# SCH_SPD_PIR_HALL.net
KiCad netlist of a schematic drawn in EasyEDA
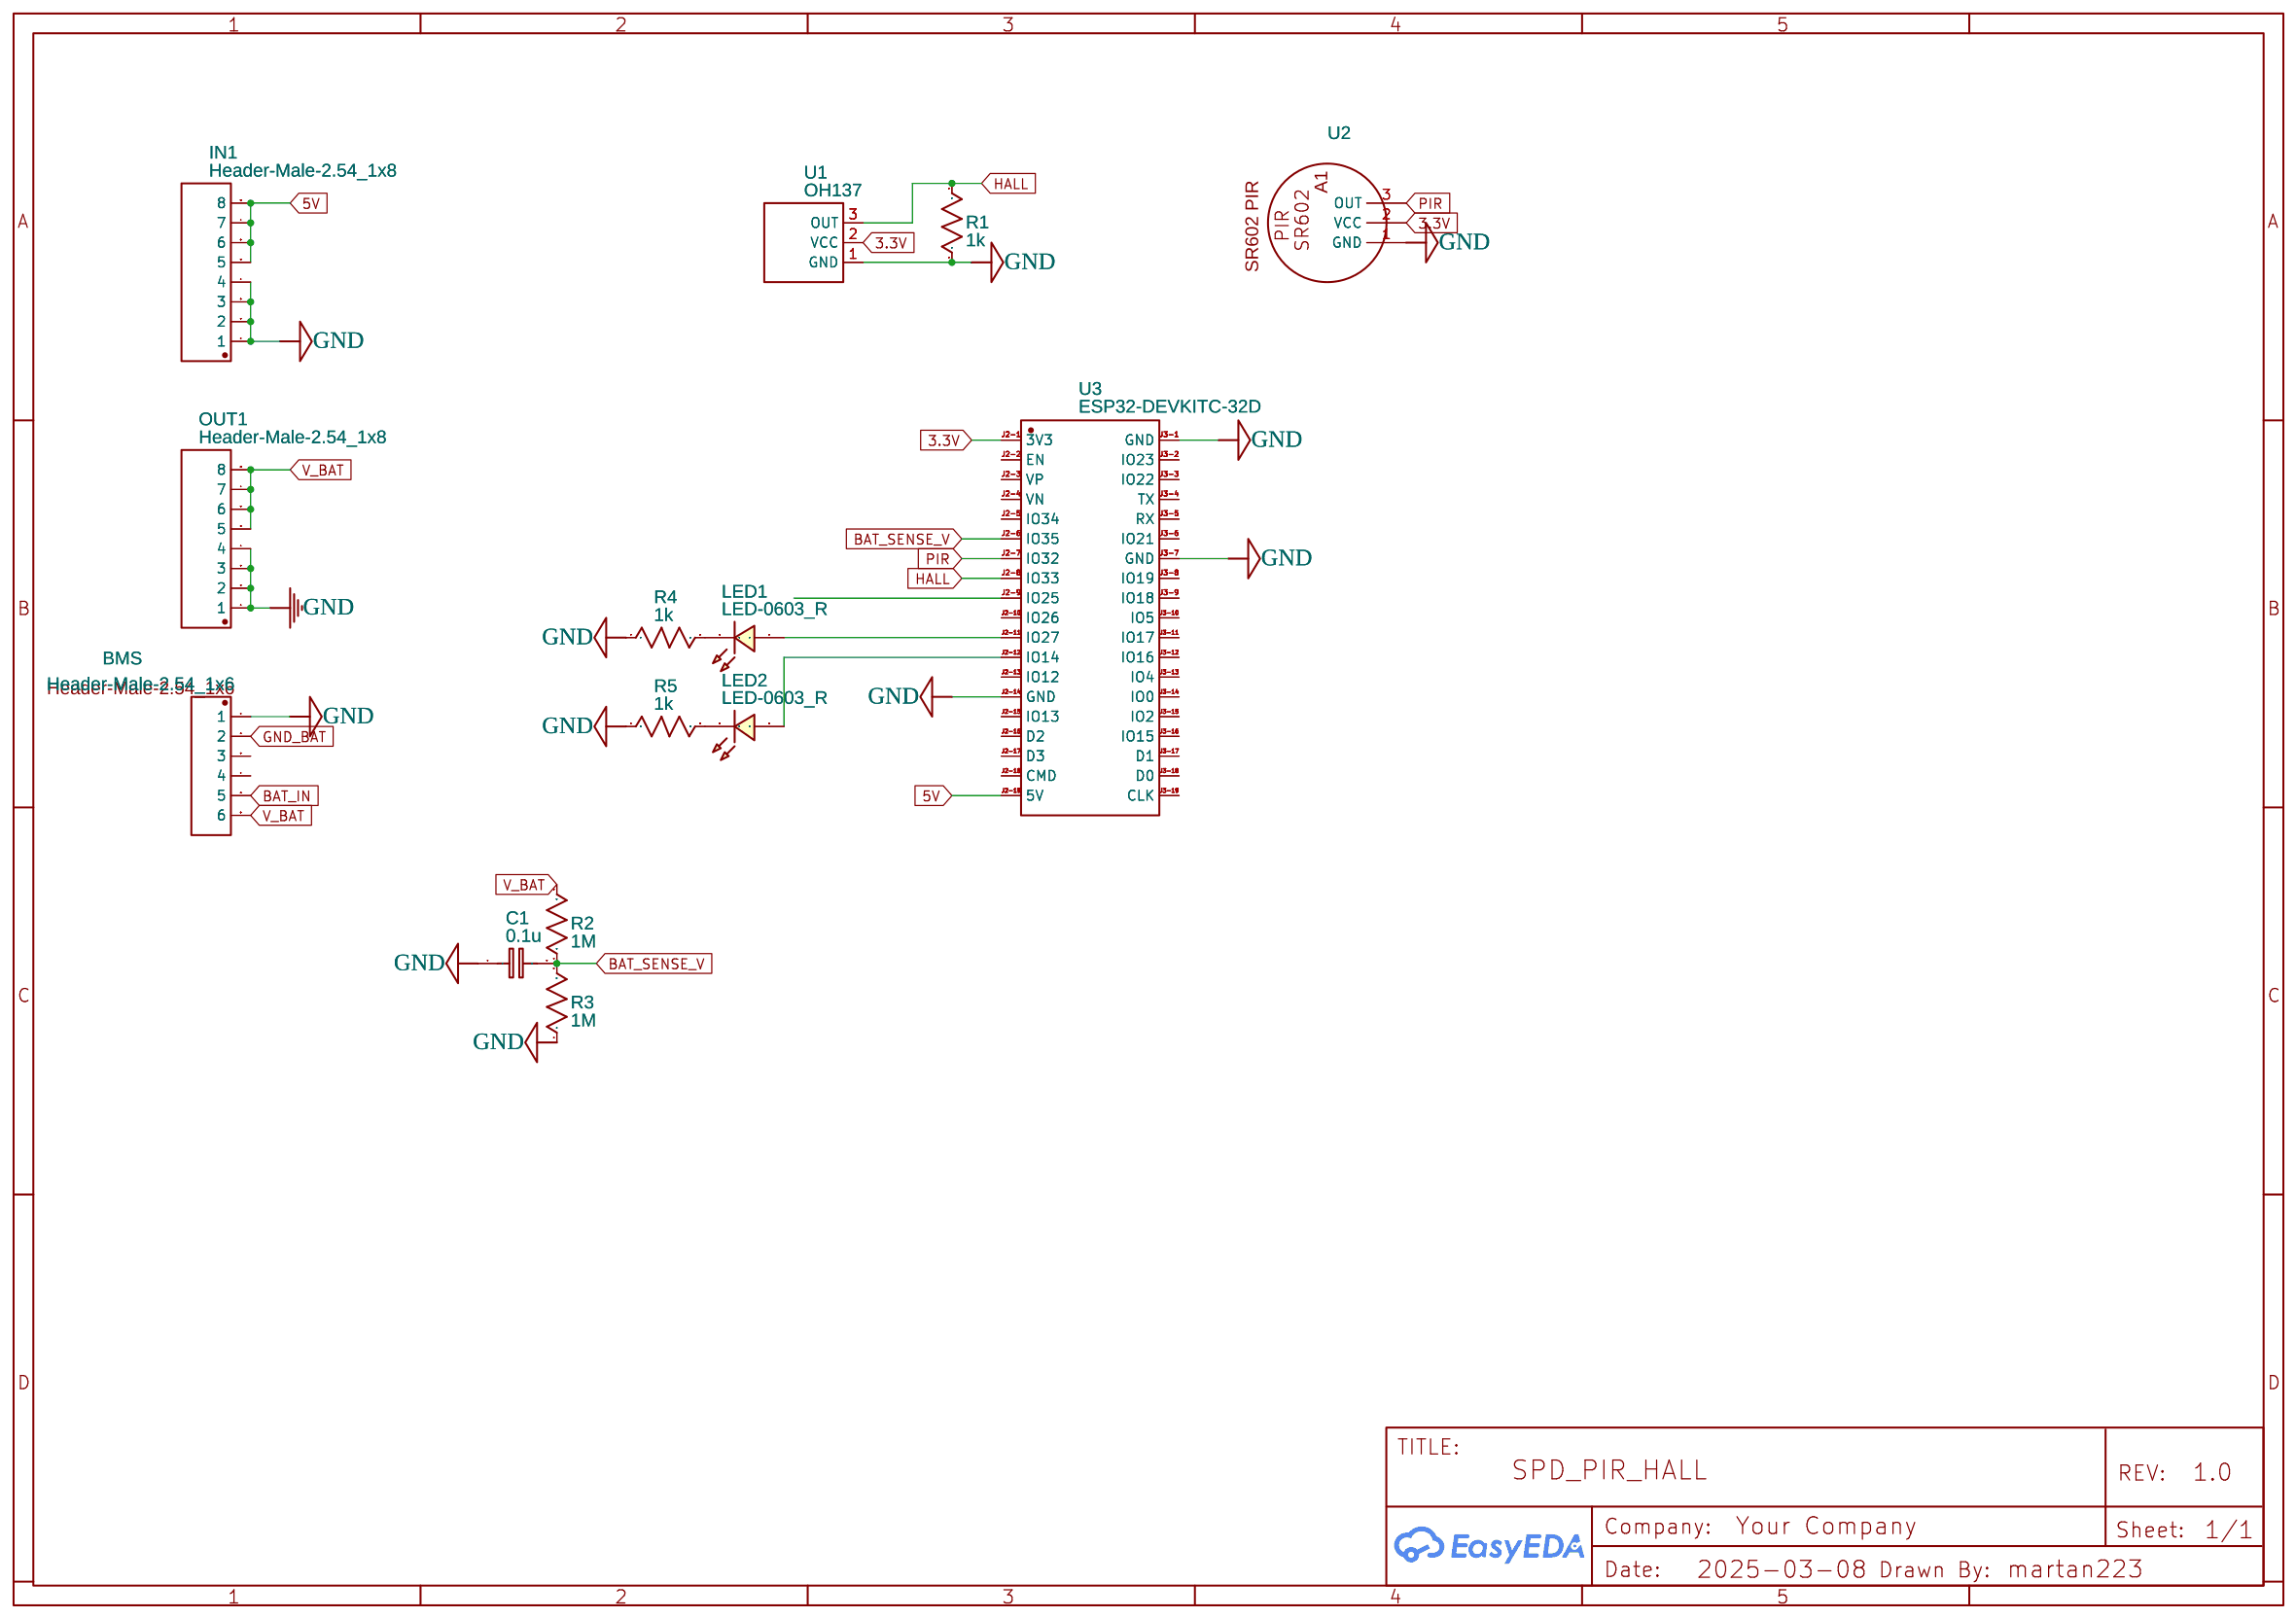
[diagram p0: schematic sheet]

(export (version "E")
  (design (tool "Eeschema 10.0.6"))
  (components
    (comp (ref "BMS") (value "Header-Male-2.54_1x6") (libsource (lib "") (part "Header-Male-2.54_1x6")))
    (comp (ref "C1") (value "0.1u") (libsource (lib "") (part "C_0603_EU")))
    (comp (ref "IN1")
      (value "Header-Male-2.54_1x8")
      (fields (field (name "Manufacturer") "Ckmtw(灿科盟)"))
      (libsource (lib "") (part "Header-Male-2.54_1x8_1"))
    )
    (comp (ref "LED1")
      (value "LED-0603_R")
      (fields
        (field (name "Manufacturer Part") "19-217/R6C-AL1M2VY/3T")
        (field (name "Manufacturer") "EVERLIGHT(台湾亿光)")
      )
      (libsource (lib "") (part "LED-0603_R"))
    )
    (comp (ref "LED2")
      (value "LED-0603_R")
      (fields
        (field (name "Manufacturer Part") "19-217/R6C-AL1M2VY/3T")
        (field (name "Manufacturer") "EVERLIGHT(台湾亿光)")
      )
      (libsource (lib "") (part "LED-0603_R"))
    )
    (comp (ref "OUT1")
      (value "Header-Male-2.54_1x8")
      (fields (field (name "Manufacturer") "Ckmtw(灿科盟)"))
      (libsource (lib "") (part "Header-Male-2.54_1x8"))
    )
    (comp (ref "R1") (value "1k") (libsource (lib "") (part "R_0603_US")))
    (comp (ref "R2") (value "1M") (libsource (lib "") (part "R_0603_US")))
    (comp (ref "R3") (value "1M") (libsource (lib "") (part "R_0603_US")))
    (comp (ref "R4") (value "1k") (libsource (lib "") (part "R_0603_US_1")))
    (comp (ref "R5") (value "1k") (libsource (lib "") (part "R_0603_US_1")))
    (comp (ref "U1")
      (value "OH137")
      (fields (field (name "Manufacturer") "南京欧卓"))
      (libsource (lib "") (part "OH137"))
    )
    (comp (ref "U2") (value "PIRSR602") (libsource (lib "") (part "PIRSR602")))
    (comp (ref "U3")
      (value "ESP32-DEVKITC-32D")
      (fields (field (name "Manufacturer") "ESPRESSIF(乐鑫)"))
      (libsource (lib "") (part "ESP32-DEVKITC-32D"))
    )
  )
  (nets
    (net (code "1") (name "3.3V") (class "Default")
      (node (ref "U1") (pin "2") (pinfunction "VCC_2") (pintype "unspecified"))
      (node (ref "U2") (pin "2") (pinfunction "VCC_2") (pintype "unspecified"))
      (node (ref "U3") (pin "J2-1") (pinfunction "3V3_J2-1") (pintype "unspecified"))
    )
    (net (code "2") (name "5V") (class "Default")
      (node (ref "IN1") (pin "5") (pinfunction "5_5") (pintype "unspecified"))
      (node (ref "IN1") (pin "6") (pinfunction "6_6") (pintype "unspecified"))
      (node (ref "IN1") (pin "7") (pinfunction "7_7") (pintype "unspecified"))
      (node (ref "IN1") (pin "8") (pinfunction "8_8") (pintype "unspecified"))
      (node (ref "U3") (pin "J2-19") (pinfunction "5V_J2-19") (pintype "unspecified"))
    )
    (net (code "3") (name "BAT_IN") (class "Default")
      (node (ref "BMS") (pin "5") (pinfunction "5_5") (pintype "unspecified"))
    )
    (net (code "4") (name "BAT_SENSE_V") (class "Default")
      (node (ref "C1") (pin "2") (pinfunction "2_2") (pintype "unspecified"))
      (node (ref "R2") (pin "1") (pinfunction "1_1") (pintype "unspecified"))
      (node (ref "R3") (pin "2") (pinfunction "2_2") (pintype "unspecified"))
      (node (ref "U3") (pin "J2-6") (pinfunction "IO35_J2-6") (pintype "unspecified"))
    )
    (net (code "5") (name "GND") (class "Default")
      (node (ref "BMS") (pin "1") (pinfunction "1_1") (pintype "unspecified"))
      (node (ref "C1") (pin "1") (pinfunction "1_1") (pintype "unspecified"))
      (node (ref "IN1") (pin "1") (pinfunction "1_1") (pintype "unspecified"))
      (node (ref "IN1") (pin "2") (pinfunction "2_2") (pintype "unspecified"))
      (node (ref "IN1") (pin "3") (pinfunction "3_3") (pintype "unspecified"))
      (node (ref "IN1") (pin "4") (pinfunction "4_4") (pintype "unspecified"))
      (node (ref "OUT1") (pin "1") (pinfunction "1_1") (pintype "unspecified"))
      (node (ref "OUT1") (pin "2") (pinfunction "2_2") (pintype "unspecified"))
      (node (ref "OUT1") (pin "3") (pinfunction "3_3") (pintype "unspecified"))
      (node (ref "OUT1") (pin "4") (pinfunction "4_4") (pintype "unspecified"))
      (node (ref "R1") (pin "1") (pinfunction "1_1") (pintype "unspecified"))
      (node (ref "R3") (pin "1") (pinfunction "1_1") (pintype "unspecified"))
      (node (ref "R4") (pin "1") (pinfunction "1_1") (pintype "unspecified"))
      (node (ref "R5") (pin "1") (pinfunction "1_1") (pintype "unspecified"))
      (node (ref "U1") (pin "1") (pinfunction "GND_1") (pintype "unspecified"))
      (node (ref "U2") (pin "1") (pinfunction "GND_1") (pintype "unspecified"))
      (node (ref "U3") (pin "J2-14") (pinfunction "GND_J2-14") (pintype "unspecified"))
      (node (ref "U3") (pin "J3-1") (pinfunction "GND_J3-1") (pintype "unspecified"))
      (node (ref "U3") (pin "J3-7") (pinfunction "GND_J3-7") (pintype "unspecified"))
    )
    (net (code "6") (name "GND_BAT") (class "Default")
      (node (ref "BMS") (pin "2") (pinfunction "2_2") (pintype "unspecified"))
    )
    (net (code "7") (name "HALL") (class "Default")
      (node (ref "R1") (pin "2") (pinfunction "2_2") (pintype "unspecified"))
      (node (ref "U1") (pin "3") (pinfunction "OUT_3") (pintype "unspecified"))
      (node (ref "U3") (pin "J2-8") (pinfunction "IO33_J2-8") (pintype "unspecified"))
    )
    (net (code "8") (name "Net-(LED1-Pad2)") (class "Default")
      (node (ref "LED1") (pin "2") (pinfunction "2_2") (pintype "unspecified"))
      (node (ref "R4") (pin "2") (pinfunction "2_2") (pintype "unspecified"))
    )
    (net (code "9") (name "Net-(LED2-Pad2)") (class "Default")
      (node (ref "LED2") (pin "2") (pinfunction "2_2") (pintype "unspecified"))
      (node (ref "R5") (pin "2") (pinfunction "2_2") (pintype "unspecified"))
    )
    (net (code "10") (name "Net-(U3-IO14)") (class "Default")
      (node (ref "LED2") (pin "1") (pinfunction "1_1") (pintype "unspecified"))
      (node (ref "U3") (pin "J2-12") (pinfunction "IO14_J2-12") (pintype "unspecified"))
    )
    (net (code "11") (name "Net-(U3-IO27)") (class "Default")
      (node (ref "LED1") (pin "1") (pinfunction "1_1") (pintype "unspecified"))
      (node (ref "U3") (pin "J2-11") (pinfunction "IO27_J2-11") (pintype "unspecified"))
    )
    (net (code "12") (name "PIR") (class "Default")
      (node (ref "U2") (pin "3") (pinfunction "OUT_3") (pintype "unspecified"))
      (node (ref "U3") (pin "J2-7") (pinfunction "IO32_J2-7") (pintype "unspecified"))
    )
    (net (code "13") (name "V_BAT") (class "Default")
      (node (ref "BMS") (pin "6") (pinfunction "6_6") (pintype "unspecified"))
      (node (ref "OUT1") (pin "5") (pinfunction "5_5") (pintype "unspecified"))
      (node (ref "OUT1") (pin "6") (pinfunction "6_6") (pintype "unspecified"))
      (node (ref "OUT1") (pin "7") (pinfunction "7_7") (pintype "unspecified"))
      (node (ref "OUT1") (pin "8") (pinfunction "8_8") (pintype "unspecified"))
      (node (ref "R2") (pin "2") (pinfunction "2_2") (pintype "unspecified"))
    )
    (net (code "14") (name "unconnected-(BMS-Pad3)") (class "Default")
      (node (ref "BMS") (pin "3") (pinfunction "3_3") (pintype "unspecified"))
    )
    (net (code "15") (name "unconnected-(BMS-Pad4)") (class "Default")
      (node (ref "BMS") (pin "4") (pinfunction "4_4") (pintype "unspecified"))
    )
    (net (code "16") (name "unconnected-(U3-CLK-PadJ3-19)") (class "Default")
      (node (ref "U3") (pin "J3-19") (pinfunction "CLK_J3-19") (pintype "unspecified"))
    )
    (net (code "17") (name "unconnected-(U3-CMD-PadJ2-18)") (class "Default")
      (node (ref "U3") (pin "J2-18") (pinfunction "CMD_J2-18") (pintype "unspecified"))
    )
    (net (code "18") (name "unconnected-(U3-D0-PadJ3-18)") (class "Default")
      (node (ref "U3") (pin "J3-18") (pinfunction "D0_J3-18") (pintype "unspecified"))
    )
    (net (code "19") (name "unconnected-(U3-D1-PadJ3-17)") (class "Default")
      (node (ref "U3") (pin "J3-17") (pinfunction "D1_J3-17") (pintype "unspecified"))
    )
    (net (code "20") (name "unconnected-(U3-D2-PadJ2-16)") (class "Default")
      (node (ref "U3") (pin "J2-16") (pinfunction "D2_J2-16") (pintype "unspecified"))
    )
    (net (code "21") (name "unconnected-(U3-D3-PadJ2-17)") (class "Default")
      (node (ref "U3") (pin "J2-17") (pinfunction "D3_J2-17") (pintype "unspecified"))
    )
    (net (code "22") (name "unconnected-(U3-EN-PadJ2-2)") (class "Default")
      (node (ref "U3") (pin "J2-2") (pinfunction "EN_J2-2") (pintype "unspecified"))
    )
    (net (code "23") (name "unconnected-(U3-IO0-PadJ3-14)") (class "Default")
      (node (ref "U3") (pin "J3-14") (pinfunction "IO0_J3-14") (pintype "unspecified"))
    )
    (net (code "24") (name "unconnected-(U3-IO2-PadJ3-15)") (class "Default")
      (node (ref "U3") (pin "J3-15") (pinfunction "IO2_J3-15") (pintype "unspecified"))
    )
    (net (code "25") (name "unconnected-(U3-IO4-PadJ3-13)") (class "Default")
      (node (ref "U3") (pin "J3-13") (pinfunction "IO4_J3-13") (pintype "unspecified"))
    )
    (net (code "26") (name "unconnected-(U3-IO5-PadJ3-10)") (class "Default")
      (node (ref "U3") (pin "J3-10") (pinfunction "IO5_J3-10") (pintype "unspecified"))
    )
    (net (code "27") (name "unconnected-(U3-IO12-PadJ2-13)") (class "Default")
      (node (ref "U3") (pin "J2-13") (pinfunction "IO12_J2-13") (pintype "unspecified"))
    )
    (net (code "28") (name "unconnected-(U3-IO13-PadJ2-15)") (class "Default")
      (node (ref "U3") (pin "J2-15") (pinfunction "IO13_J2-15") (pintype "unspecified"))
    )
    (net (code "29") (name "unconnected-(U3-IO15-PadJ3-16)") (class "Default")
      (node (ref "U3") (pin "J3-16") (pinfunction "IO15_J3-16") (pintype "unspecified"))
    )
    (net (code "30") (name "unconnected-(U3-IO16-PadJ3-12)") (class "Default")
      (node (ref "U3") (pin "J3-12") (pinfunction "IO16_J3-12") (pintype "unspecified"))
    )
    (net (code "31") (name "unconnected-(U3-IO17-PadJ3-11)") (class "Default")
      (node (ref "U3") (pin "J3-11") (pinfunction "IO17_J3-11") (pintype "unspecified"))
    )
    (net (code "32") (name "unconnected-(U3-IO18-PadJ3-9)") (class "Default")
      (node (ref "U3") (pin "J3-9") (pinfunction "IO18_J3-9") (pintype "unspecified"))
    )
    (net (code "33") (name "unconnected-(U3-IO19-PadJ3-8)") (class "Default")
      (node (ref "U3") (pin "J3-8") (pinfunction "IO19_J3-8") (pintype "unspecified"))
    )
    (net (code "34") (name "unconnected-(U3-IO21-PadJ3-6)") (class "Default")
      (node (ref "U3") (pin "J3-6") (pinfunction "IO21_J3-6") (pintype "unspecified"))
    )
    (net (code "35") (name "unconnected-(U3-IO22-PadJ3-3)") (class "Default")
      (node (ref "U3") (pin "J3-3") (pinfunction "IO22_J3-3") (pintype "unspecified"))
    )
    (net (code "36") (name "unconnected-(U3-IO23-PadJ3-2)") (class "Default")
      (node (ref "U3") (pin "J3-2") (pinfunction "IO23_J3-2") (pintype "unspecified"))
    )
    (net (code "37") (name "unconnected-(U3-IO25-PadJ2-9)") (class "Default")
      (node (ref "U3") (pin "J2-9") (pinfunction "IO25_J2-9") (pintype "unspecified"))
    )
    (net (code "38") (name "unconnected-(U3-IO26-PadJ2-10)") (class "Default")
      (node (ref "U3") (pin "J2-10") (pinfunction "IO26_J2-10") (pintype "unspecified"))
    )
    (net (code "39") (name "unconnected-(U3-IO34-PadJ2-5)") (class "Default")
      (node (ref "U3") (pin "J2-5") (pinfunction "IO34_J2-5") (pintype "unspecified"))
    )
    (net (code "40") (name "unconnected-(U3-RX-PadJ3-5)") (class "Default")
      (node (ref "U3") (pin "J3-5") (pinfunction "RX_J3-5") (pintype "unspecified"))
    )
    (net (code "41") (name "unconnected-(U3-TX-PadJ3-4)") (class "Default")
      (node (ref "U3") (pin "J3-4") (pinfunction "TX_J3-4") (pintype "unspecified"))
    )
    (net (code "42") (name "unconnected-(U3-VN-PadJ2-4)") (class "Default")
      (node (ref "U3") (pin "J2-4") (pinfunction "VN_J2-4") (pintype "unspecified"))
    )
    (net (code "43") (name "unconnected-(U3-VP-PadJ2-3)") (class "Default")
      (node (ref "U3") (pin "J2-3") (pinfunction "VP_J2-3") (pintype "unspecified"))
    )
  )
)
